# Powerjack_LED.net
KiCad netlist of a schematic drawn in Altium Designer
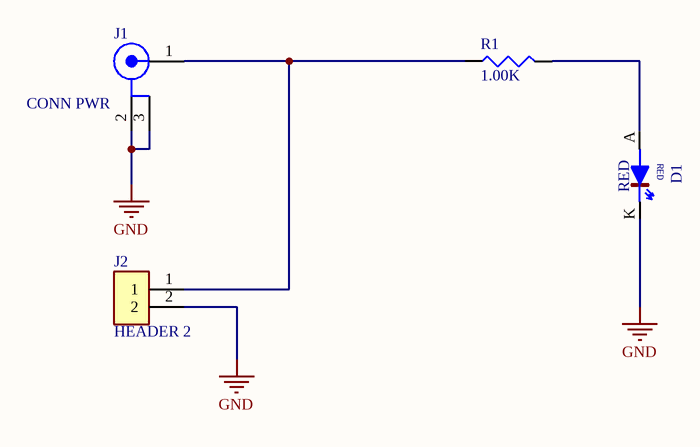
[diagram p0: Powerjack_LED.SchDoc]

(export (version "E")
  (design (tool "Eeschema 10.0.6"))
  (components
    (comp (ref "D1")
      (value "RED")
      (footprint "LED-0805-RED")
      (description "LED RED CLEAR 0805 SMD")
      (fields (field (name "MANUFACTURER") "LITE-On Inc.") (field (name "PART_NUMBER") "LTST-C171KRKT"))
      (libsource (lib "ST365  R1.2") (part "LTST-C191KRKT"))
    )
    (comp (ref "J1")
      (value "CONN PWR")
      (footprint "EJ508A")
      (description "CONN PWR JACK 2.1X5.5MM SOLDER")
      (fields
        (field (name "MANUFACTURER") "MPD (Memory Protection Devices)")
        (field (name "PART_NUMBER") "EJ508A")
      )
      (libsource (lib "ST365  R1.2") (part "CONN - BNC-EJ508A"))
    )
    (comp (ref "J2")
      (value "HEADER 2")
      (footprint "TSW-102-07-G-S")
      (description "CONN HEADER 2POS .100\" SGL GOLD")
      (fields (field (name "MANUFACTURER") "Samtec Inc.") (field (name "PART_NUMBER") "TSW-102-07-G-S"))
      (libsource (lib "ST365  R1.2") (part "TSW-102-07-G-S"))
    )
    (comp (ref "R1")
      (value "1.00K")
      (footprint "0805-R")
      (description "RES SMD 1K OHM 1% 1/8W 0805")
      (fields (field (name "MANUFACTURER") "Yageo") (field (name "PART_NUMBER") "RC0805FR-071KL"))
      (libsource (lib "ST365  R1.2") (part "RES 1.00K 1P0 0805"))
    )
  )
  (nets
    (net (code "1") (name "GND") (class "Default")
      (node (ref "D1") (pin "K") (pinfunction "K_K") (pintype "passive"))
      (node (ref "J1") (pin "2") (pinfunction "SHIELD_2") (pintype "passive"))
      (node (ref "J1") (pin "3") (pinfunction "SHIELD_3") (pintype "passive"))
      (node (ref "J2") (pin "2") (pinfunction "2_2") (pintype "passive"))
    )
    (net (code "2") (name "Net-(D1-PadA)") (class "Default")
      (node (ref "D1") (pin "A") (pinfunction "A_A") (pintype "passive"))
      (node (ref "R1") (pin "2") (pinfunction "2_2") (pintype "passive"))
    )
    (net (code "3") (name "Net-(J1-CENTER)") (class "Default")
      (node (ref "J1") (pin "1") (pinfunction "CENTER_1") (pintype "passive"))
      (node (ref "J2") (pin "1") (pinfunction "1_1") (pintype "passive"))
      (node (ref "R1") (pin "1") (pinfunction "1_1") (pintype "passive"))
    )
  )
)
